# thermostat_hardwork.net
KiCad netlist of a schematic drawn in EasyEDA Pro
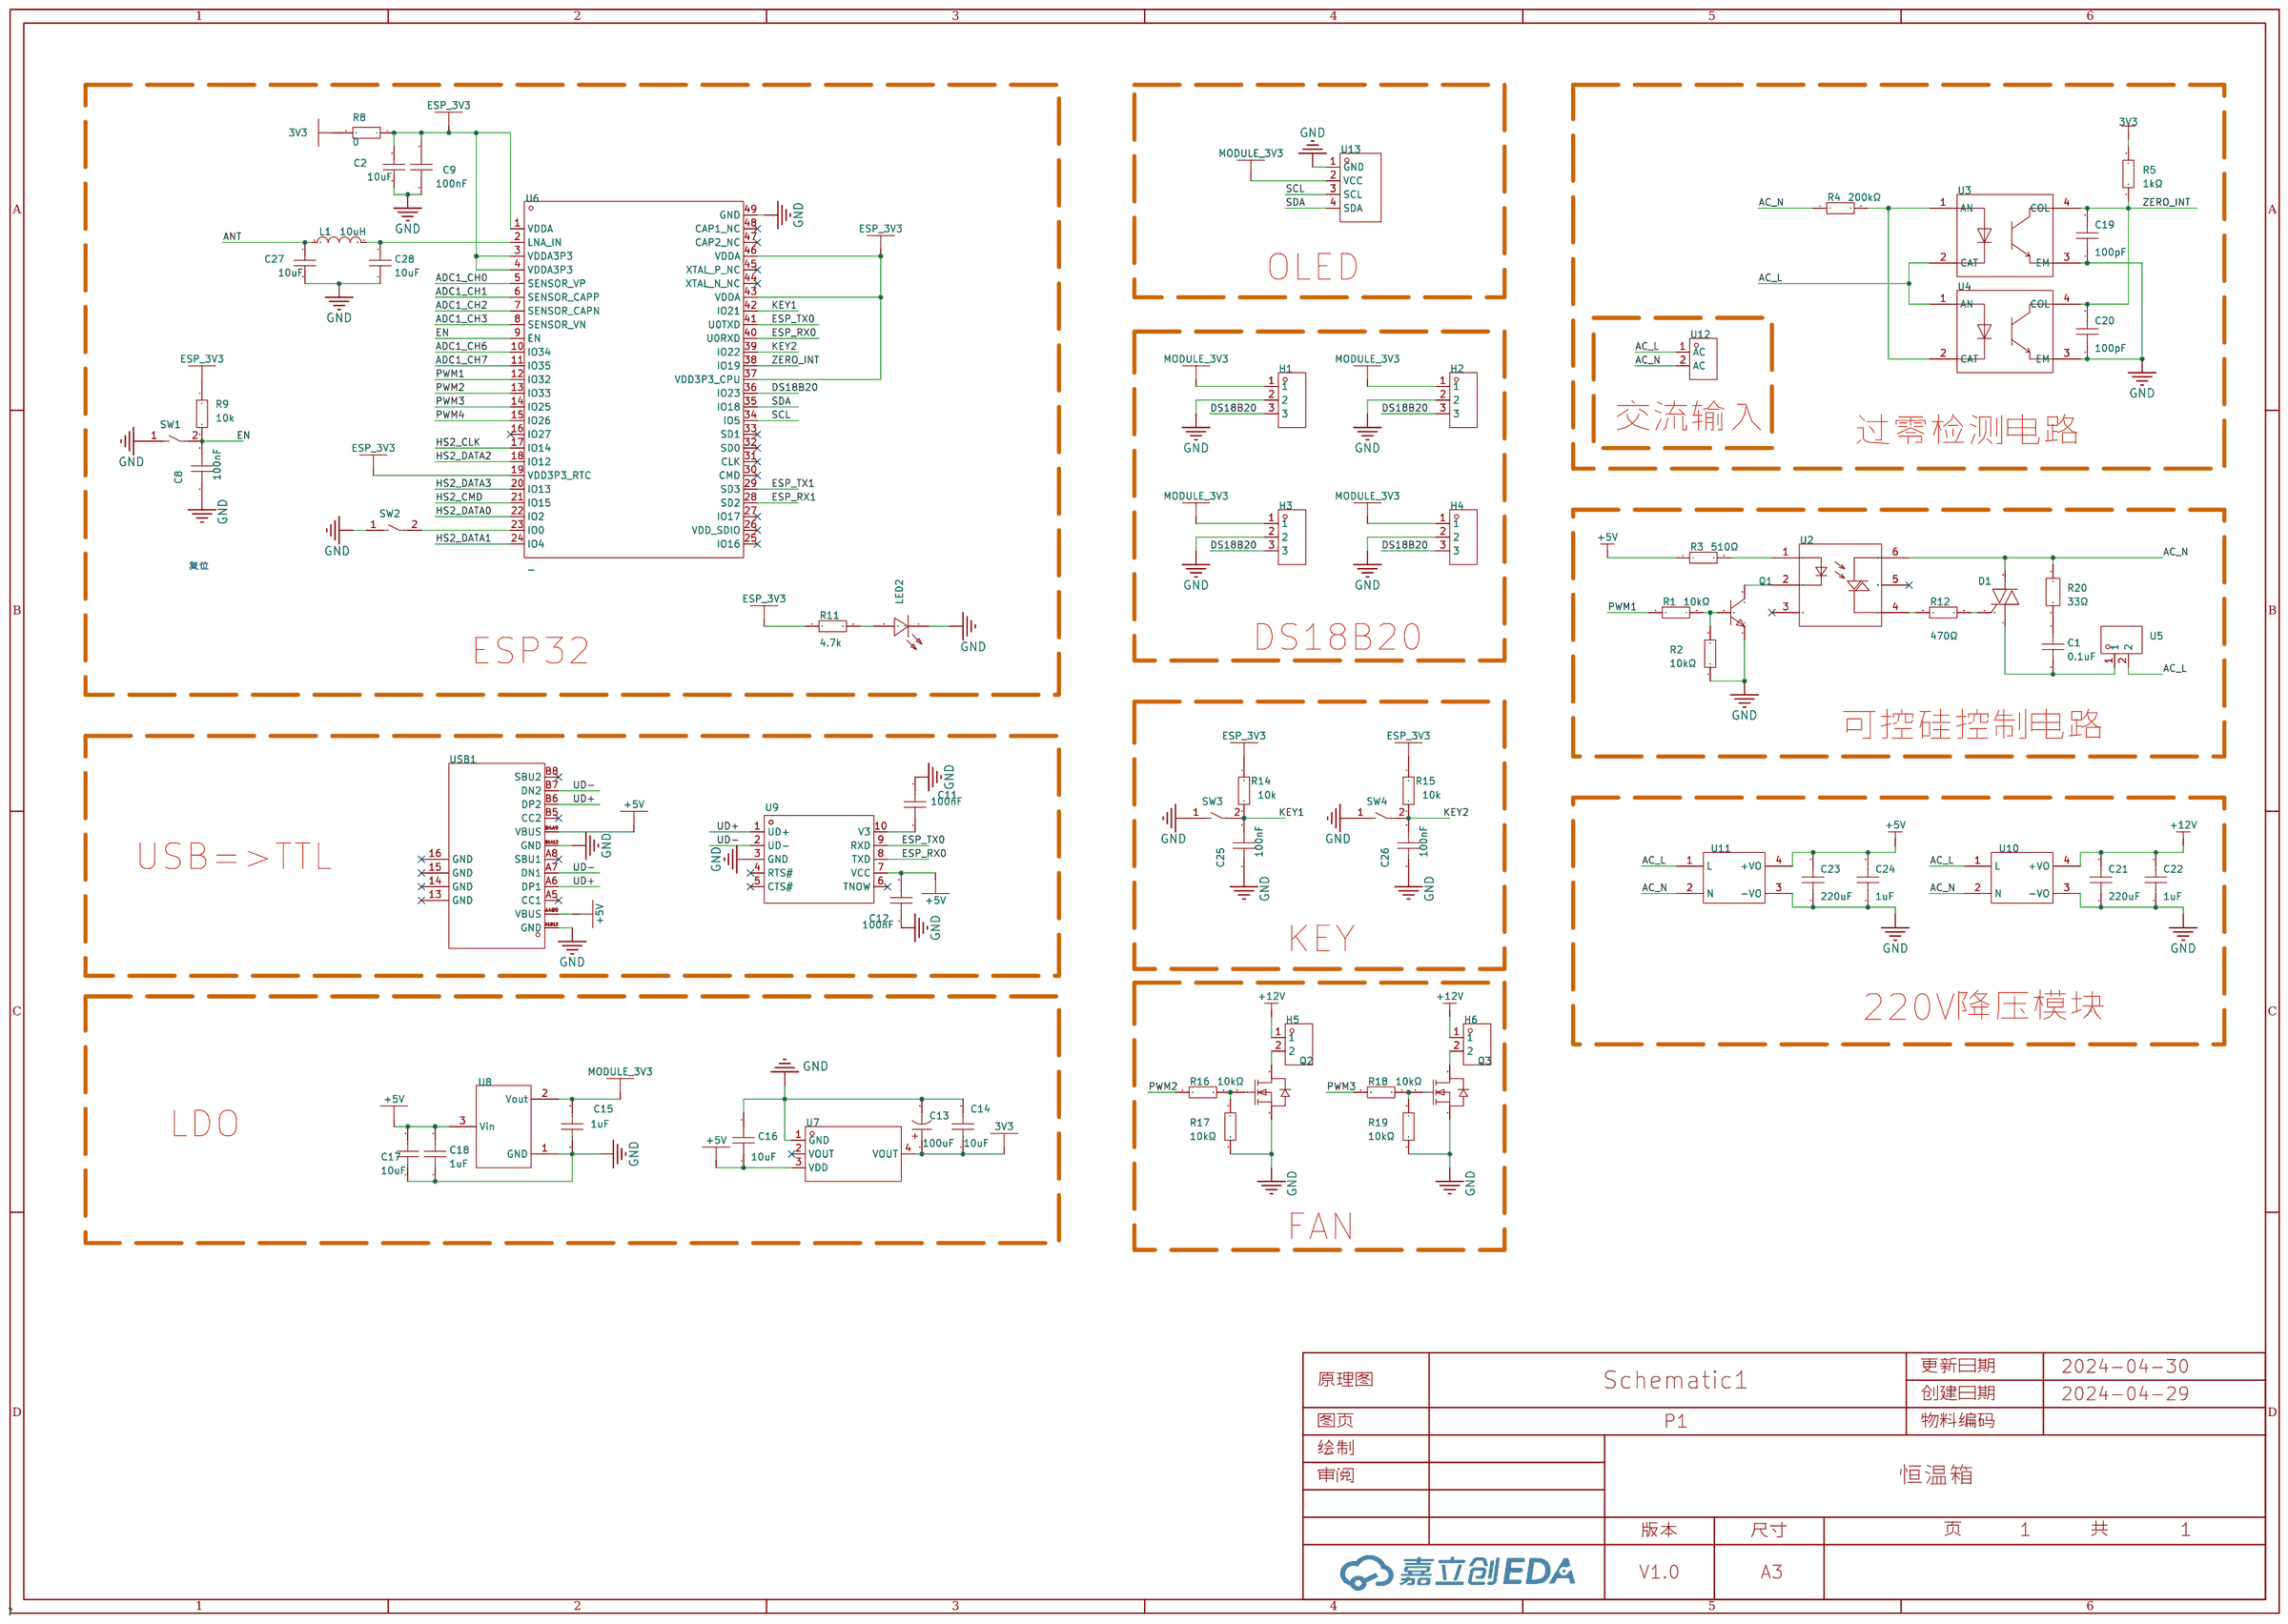
[diagram p0: schematic sheet]

(export (version "E")
  (design (tool "Eeschema 10.0.6"))
  (components
    (comp (ref "C1")
      (value "0.1uF")
      (footprint "easyedapro:C1210")
      (description "容值:10nF;精度:±5%;额定电压:250V;材质(温度系数):C0G;")
      (fields (field (name "Manufacturer Part") "C3225C0G2E103JT000N") (field (name "Manufacturer") "TDK"))
      (libsource (lib "easyedapro") (part "C3225C0G2E103JT000N"))
    )
    (comp (ref "C2")
      (value "10uF")
      (footprint "easyedapro:C0402")
      (description "容值:10uF;精度:±20%;额定电压:6.3V;温度系数:X5R;")
      (fields
        (field (name "Manufacturer Part") "CC0402MRX5R5BB106")
        (field (name "Manufacturer") "YAGEO(国巨)")
      )
      (libsource (lib "easyedapro") (part "CC0402MRX5R5BB106"))
    )
    (comp (ref "C8")
      (value "100nF")
      (description "容值:100nF;精度:±5%;额定电压:16V;温度系数:X7R;")
      (fields
        (field (name "Manufacturer Part") "CC0402JRX7R7BB104")
        (field (name "Manufacturer") "YAGEO(国巨)")
      )
      (libsource (lib "easyedapro") (part "CC0402JRX7R7BB104"))
    )
    (comp (ref "C9")
      (value "100nF")
      (description "容值:100nF;精度:±5%;额定电压:16V;温度系数:X7R;")
      (fields
        (field (name "Manufacturer Part") "CC0402JRX7R7BB104")
        (field (name "Manufacturer") "YAGEO(国巨)")
      )
      (libsource (lib "easyedapro") (part "CC0402JRX7R7BB104"))
    )
    (comp (ref "C11")
      (value "100nF")
      (description "容值:100nF;精度:±5%;额定电压:16V;温度系数:X7R;")
      (fields
        (field (name "Manufacturer Part") "CC0402JRX7R7BB104")
        (field (name "Manufacturer") "YAGEO(国巨)")
      )
      (libsource (lib "easyedapro") (part "CC0402JRX7R7BB104"))
    )
    (comp (ref "C12")
      (value "100nF")
      (description "容值:100nF;精度:±5%;额定电压:16V;温度系数:X7R;")
      (fields
        (field (name "Manufacturer Part") "CC0402JRX7R7BB104")
        (field (name "Manufacturer") "YAGEO(国巨)")
      )
      (libsource (lib "easyedapro") (part "CC0402JRX7R7BB104"))
    )
    (comp (ref "C13")
      (value "100uF")
      (description "容值:100uF;精度:±20%;额定电压:6.3V;等效串联电阻:-;工作温度:-55~+125;")
      (fields
        (field (name "Manufacturer Part") "CA45B-B-6.3V-100uF-M")
        (field (name "Manufacturer") "CEC(振华新云)")
      )
      (libsource (lib "easyedapro") (part "CA45B-B-6.3V-100UF-M"))
    )
    (comp (ref "C14")
      (value "10uF")
      (description "容值:10uF;精度:±10%;额定电压:10V;温度系数:X5R;")
      (fields
        (field (name "Manufacturer Part") "CL10A106KP8NNNC")
        (field (name "Manufacturer") "SAMSUNG(三星)")
      )
      (libsource (lib "easyedapro") (part "CL10A106KP8NNNC"))
    )
    (comp (ref "C15")
      (value "1uF")
      (footprint "easyedapro:C0402")
      (description "容值:1uF;精度:±10%;额定电压:10V;温度系数:X7R;")
      (fields
        (field (name "Manufacturer Part") "GRM155Z71A105KE01D")
        (field (name "Manufacturer") "muRata(村田)")
      )
      (libsource (lib "easyedapro") (part "GRM155Z71A105KE01D"))
    )
    (comp (ref "C16")
      (value "10uF")
      (description "容值:10uF;精度:±10%;额定电压:10V;温度系数:X5R;")
      (fields
        (field (name "Manufacturer Part") "CL10A106KP8NNNC")
        (field (name "Manufacturer") "SAMSUNG(三星)")
      )
      (libsource (lib "easyedapro") (part "CL10A106KP8NNNC"))
    )
    (comp (ref "C17")
      (value "10uF")
      (description "容值:10uF;精度:±10%;额定电压:10V;温度系数:X5R;")
      (fields
        (field (name "Manufacturer Part") "CL10A106KP8NNNC")
        (field (name "Manufacturer") "SAMSUNG(三星)")
      )
      (libsource (lib "easyedapro") (part "CL10A106KP8NNNC"))
    )
    (comp (ref "C18")
      (value "1uF")
      (footprint "easyedapro:C0402")
      (description "容值:1uF;精度:±10%;额定电压:10V;温度系数:X7R;")
      (fields
        (field (name "Manufacturer Part") "GRM155Z71A105KE01D")
        (field (name "Manufacturer") "muRata(村田)")
      )
      (libsource (lib "easyedapro") (part "GRM155Z71A105KE01D"))
    )
    (comp (ref "C19")
      (value "100pF")
      (description "容值:100nF;精度:±5%;额定电压:16V;温度系数:X7R;")
      (fields
        (field (name "Manufacturer Part") "CC0402JRX7R7BB104")
        (field (name "Manufacturer") "YAGEO(国巨)")
      )
      (libsource (lib "easyedapro") (part "CC0402JRX7R7BB104"))
    )
    (comp (ref "C20")
      (value "100pF")
      (description "容值:100nF;精度:±5%;额定电压:16V;温度系数:X7R;")
      (fields
        (field (name "Manufacturer Part") "CC0402JRX7R7BB104")
        (field (name "Manufacturer") "YAGEO(国巨)")
      )
      (libsource (lib "easyedapro") (part "CC0402JRX7R7BB104"))
    )
    (comp (ref "C21")
      (value "220uF")
      (description "容值:100nF;精度:±5%;额定电压:16V;温度系数:X7R;")
      (fields
        (field (name "Manufacturer Part") "CC0402JRX7R7BB104")
        (field (name "Manufacturer") "YAGEO(国巨)")
      )
      (libsource (lib "easyedapro") (part "CC0402JRX7R7BB104"))
    )
    (comp (ref "C22")
      (value "1uF")
      (description "容值:100nF;精度:±5%;额定电压:16V;温度系数:X7R;")
      (fields
        (field (name "Manufacturer Part") "CC0402JRX7R7BB104")
        (field (name "Manufacturer") "YAGEO(国巨)")
      )
      (libsource (lib "easyedapro") (part "CC0402JRX7R7BB104"))
    )
    (comp (ref "C23")
      (value "220uF")
      (description "容值:100nF;精度:±5%;额定电压:16V;温度系数:X7R;")
      (fields
        (field (name "Manufacturer Part") "CC0402JRX7R7BB104")
        (field (name "Manufacturer") "YAGEO(国巨)")
      )
      (libsource (lib "easyedapro") (part "CC0402JRX7R7BB104"))
    )
    (comp (ref "C24")
      (value "1uF")
      (description "容值:100nF;精度:±5%;额定电压:16V;温度系数:X7R;")
      (fields
        (field (name "Manufacturer Part") "CC0402JRX7R7BB104")
        (field (name "Manufacturer") "YAGEO(国巨)")
      )
      (libsource (lib "easyedapro") (part "CC0402JRX7R7BB104"))
    )
    (comp (ref "C25")
      (value "100nF")
      (description "容值:100nF;精度:±5%;额定电压:16V;温度系数:X7R;")
      (fields
        (field (name "Manufacturer Part") "CC0402JRX7R7BB104")
        (field (name "Manufacturer") "YAGEO(国巨)")
      )
      (libsource (lib "easyedapro") (part "CC0402JRX7R7BB104"))
    )
    (comp (ref "C26")
      (value "100nF")
      (description "容值:100nF;精度:±5%;额定电压:16V;温度系数:X7R;")
      (fields
        (field (name "Manufacturer Part") "CC0402JRX7R7BB104")
        (field (name "Manufacturer") "YAGEO(国巨)")
      )
      (libsource (lib "easyedapro") (part "CC0402JRX7R7BB104"))
    )
    (comp (ref "C27")
      (value "10uF")
      (footprint "easyedapro:C0402")
      (description "容值:10uF;精度:±20%;额定电压:6.3V;温度系数:X5R;")
      (fields
        (field (name "Manufacturer Part") "CC0402MRX5R5BB106")
        (field (name "Manufacturer") "YAGEO(国巨)")
      )
      (libsource (lib "easyedapro") (part "CC0402MRX5R5BB106"))
    )
    (comp (ref "C28")
      (value "10uF")
      (footprint "easyedapro:C0402")
      (description "容值:10uF;精度:±20%;额定电压:6.3V;温度系数:X5R;")
      (fields
        (field (name "Manufacturer Part") "CC0402MRX5R5BB106")
        (field (name "Manufacturer") "YAGEO(国巨)")
      )
      (libsource (lib "easyedapro") (part "CC0402MRX5R5BB106"))
    )
    (comp (ref "D1")
      (value "BT136S")
      (footprint "easyedapro:TO-252-3_L6.5-W5.8-P4.58-BL")
      (description "长电双向可控硅")
      (fields (field (name "Manufacturer") "CJ(江苏长电/长晶)"))
      (libsource (lib "easyedapro") (part "BT136S"))
    )
    (comp (ref "H1")
      (value "PZ254V-11-03P")
      (footprint "easyedapro:HDR-TH_3P-P2.54-V-M")
      (fields (field (name "Manufacturer") "XFCN(兴飞)"))
      (libsource (lib "easyedapro") (part "PZ254V-11-03P_C2937625"))
    )
    (comp (ref "H2")
      (value "PZ254V-11-03P")
      (footprint "easyedapro:HDR-TH_3P-P2.54-V-M")
      (fields (field (name "Manufacturer") "XFCN(兴飞)"))
      (libsource (lib "easyedapro") (part "PZ254V-11-03P_C2937625"))
    )
    (comp (ref "H3")
      (value "PZ254V-11-03P")
      (footprint "easyedapro:HDR-TH_3P-P2.54-V-M")
      (fields (field (name "Manufacturer") "XFCN(兴飞)"))
      (libsource (lib "easyedapro") (part "PZ254V-11-03P_C2937625"))
    )
    (comp (ref "H4")
      (value "PZ254V-11-03P")
      (footprint "easyedapro:HDR-TH_3P-P2.54-V-M")
      (fields (field (name "Manufacturer") "XFCN(兴飞)"))
      (libsource (lib "easyedapro") (part "PZ254V-11-03P_C2937625"))
    )
    (comp (ref "H5")
      (value "PZ254V-11-02P")
      (footprint "easyedapro:HDR-TH_2P-P2.54-V-M")
      (fields (field (name "Manufacturer") "XFCN(兴飞)"))
      (libsource (lib "easyedapro") (part "PZ254V-11-02P"))
    )
    (comp (ref "H6")
      (value "PZ254V-11-02P")
      (footprint "easyedapro:HDR-TH_2P-P2.54-V-M")
      (fields (field (name "Manufacturer") "XFCN(兴飞)"))
      (libsource (lib "easyedapro") (part "PZ254V-11-02P"))
    )
    (comp (ref "L1")
      (value "10uH")
      (footprint "easyedapro:L0603")
      (description "电感值:10uH;精度:±10%;额定电流:280mA;直流电阻(DCR):2.4Ω;")
      (fields (field (name "Manufacturer Part") "AHW1608FE100KTF") (field (name "Manufacturer") "APV(爱普微)"))
      (libsource (lib "easyedapro") (part "AHW1608FE100KTF"))
    )
    (comp (ref "LED2")
      (value "~")
      (description "发光颜色:翠绿;")
      (fields (field (name "Manufacturer Part") "NCD0402G1") (field (name "Manufacturer") "国星光电"))
      (libsource (lib "easyedapro") (part "FC-F1005UGK-520M5"))
    )
    (comp (ref "Q1")
      (value "S8050")
      (footprint "easyedapro:SOT-23-3_L2.9-W1.3-P1.90-LS2.4-BR")
      (description "晶体管类型:NPN;集电极电流(Ic):500mA;集射极击穿电压(Vceo):25V;功率(Pd):300mW;")
      (fields (field (name "Manufacturer") "YONGYUTAI(永裕泰)"))
      (libsource (lib "easyedapro") (part "S8050_C2891804"))
    )
    (comp (ref "Q2")
      (value "AO3400A")
      (footprint "easyedapro:SOT-23-3_L2.9-W1.6-P1.90-LS2.8-BR")
      (fields (field (name "Manufacturer") "AOS"))
      (libsource (lib "easyedapro") (part "AO3400A"))
    )
    (comp (ref "Q3")
      (value "AO3400A")
      (footprint "easyedapro:SOT-23-3_L2.9-W1.6-P1.90-LS2.8-BR")
      (fields (field (name "Manufacturer") "AOS"))
      (libsource (lib "easyedapro") (part "AO3400A"))
    )
    (comp (ref "R1")
      (value "10kΩ")
      (footprint "easyedapro:R0603")
      (description "电阻类型:厚膜电阻;阻值:10kΩ;精度:±1%;功率:100mW;最大工作电压:75V;温度系数:±100ppm/°C;")
      (fields
        (field (name "Manufacturer Part") "0603WAF1002T5E")
        (field (name "Manufacturer") "UNI-ROYAL(厚声)")
      )
      (libsource (lib "easyedapro") (part "0603WAF1002T5E"))
    )
    (comp (ref "R2")
      (value "10kΩ")
      (footprint "easyedapro:R0603")
      (description "电阻类型:厚膜电阻;阻值:10kΩ;精度:±1%;功率:100mW;最大工作电压:75V;温度系数:±100ppm/°C;")
      (fields
        (field (name "Manufacturer Part") "0603WAF1002T5E")
        (field (name "Manufacturer") "UNI-ROYAL(厚声)")
      )
      (libsource (lib "easyedapro") (part "0603WAF1002T5E"))
    )
    (comp (ref "R3")
      (value "510Ω")
      (footprint "easyedapro:R0603")
      (description "电阻类型:厚膜电阻;阻值:10kΩ;精度:±1%;功率:100mW;最大工作电压:75V;温度系数:±100ppm/°C;")
      (fields
        (field (name "Manufacturer Part") "0603WAF1002T5E")
        (field (name "Manufacturer") "UNI-ROYAL(厚声)")
      )
      (libsource (lib "easyedapro") (part "0603WAF1002T5E"))
    )
    (comp (ref "R4")
      (value "200kΩ")
      (footprint "easyedapro:R0603")
      (description "电阻类型:厚膜电阻;阻值:200kΩ;精度:±1%;功率:100mW;最大工作电压:75V;温度系数:±100ppm/°C;")
      (fields
        (field (name "Manufacturer Part") "0603WAF2003T5E")
        (field (name "Manufacturer") "UNI-ROYAL(厚声)")
      )
      (libsource (lib "easyedapro") (part "0603WAF2003T5E"))
    )
    (comp (ref "R5")
      (value "1kΩ")
      (footprint "easyedapro:R0603")
      (description "电阻类型:厚膜电阻;阻值:1kΩ;精度:±1%;功率:100mW;最大工作电压:75V;温度系数:±100ppm/°C;")
      (fields (field (name "Manufacturer Part") "RC0603FR-071KL") (field (name "Manufacturer") "YAGEO(国巨)"))
      (libsource (lib "easyedapro") (part "RC0603FR-071KL"))
    )
    (comp (ref "R8")
      (value "0")
      (description "电阻类型:厚膜电阻;阻值:0;精度:±5%;功率:1/16W;温度系数:-;最大工作电压:50V;工作温度范围:-55~+155;")
      (fields
        (field (name "Manufacturer Part") "0402WGJ0000TCE")
        (field (name "Manufacturer") "UNI-ROYAL(厚声)")
      )
      (libsource (lib "easyedapro") (part "0402WGJ0000TCE"))
    )
    (comp (ref "R9")
      (value "10k")
      (description "电阻类型:厚膜电阻;阻值:10k;精度:±1%;功率:62.5mW;温度系数:±100ppm/;最大工作电压:50V;工作温度范围:-55~+155;")
      (fields (field (name "Manufacturer Part") "AC0402FR-0710KL") (field (name "Manufacturer") "YAGEO(国巨)"))
      (libsource (lib "easyedapro") (part "AC0402FR-0710KL"))
    )
    (comp (ref "R11")
      (value "4.7k")
      (description "电阻类型:厚膜电阻;阻值:4.7k;精度:±1%;功率:62.5mW;温度系数:±100ppm/;最大工作电压:50V;工作温度范围:-55~+155;")
      (fields (field (name "Manufacturer Part") "AC0402FR-074K7L") (field (name "Manufacturer") "YAGEO(国巨)"))
      (libsource (lib "easyedapro") (part "AC0402FR-074K7L"))
    )
    (comp (ref "R12")
      (value "470Ω")
      (footprint "easyedapro:R1206")
      (description "电阻类型:厚膜电阻;阻值:22Ω;精度:±1%;功率:250mW;最大工作电压:200V;温度系数:±100ppm/°C;")
      (fields
        (field (name "Manufacturer Part") "1206W4F220JT5E")
        (field (name "Manufacturer") "UNI-ROYAL(厚声)")
      )
      (libsource (lib "easyedapro") (part "1206W4F220JT5E"))
    )
    (comp (ref "R14")
      (value "10k")
      (description "电阻类型:厚膜电阻;阻值:10k;精度:±1%;功率:62.5mW;温度系数:±100ppm/;最大工作电压:50V;工作温度范围:-55~+155;")
      (fields (field (name "Manufacturer Part") "AC0402FR-0710KL") (field (name "Manufacturer") "YAGEO(国巨)"))
      (libsource (lib "easyedapro") (part "AC0402FR-0710KL"))
    )
    (comp (ref "R15")
      (value "10k")
      (description "电阻类型:厚膜电阻;阻值:10k;精度:±1%;功率:62.5mW;温度系数:±100ppm/;最大工作电压:50V;工作温度范围:-55~+155;")
      (fields (field (name "Manufacturer Part") "AC0402FR-0710KL") (field (name "Manufacturer") "YAGEO(国巨)"))
      (libsource (lib "easyedapro") (part "AC0402FR-0710KL"))
    )
    (comp (ref "R16")
      (value "10kΩ")
      (footprint "easyedapro:R0603")
      (description "电阻类型:厚膜电阻;阻值:10kΩ;精度:±1%;功率:100mW;最大工作电压:75V;温度系数:±100ppm/°C;")
      (fields
        (field (name "Manufacturer Part") "0603WAF1002T5E")
        (field (name "Manufacturer") "UNI-ROYAL(厚声)")
      )
      (libsource (lib "easyedapro") (part "0603WAF1002T5E"))
    )
    (comp (ref "R17")
      (value "10kΩ")
      (footprint "easyedapro:R0603")
      (description "电阻类型:厚膜电阻;阻值:10kΩ;精度:±1%;功率:100mW;最大工作电压:75V;温度系数:±100ppm/°C;")
      (fields
        (field (name "Manufacturer Part") "0603WAF1002T5E")
        (field (name "Manufacturer") "UNI-ROYAL(厚声)")
      )
      (libsource (lib "easyedapro") (part "0603WAF1002T5E"))
    )
    (comp (ref "R18")
      (value "10kΩ")
      (footprint "easyedapro:R0603")
      (description "电阻类型:厚膜电阻;阻值:10kΩ;精度:±1%;功率:100mW;最大工作电压:75V;温度系数:±100ppm/°C;")
      (fields
        (field (name "Manufacturer Part") "0603WAF1002T5E")
        (field (name "Manufacturer") "UNI-ROYAL(厚声)")
      )
      (libsource (lib "easyedapro") (part "0603WAF1002T5E"))
    )
    (comp (ref "R19")
      (value "10kΩ")
      (footprint "easyedapro:R0603")
      (description "电阻类型:厚膜电阻;阻值:10kΩ;精度:±1%;功率:100mW;最大工作电压:75V;温度系数:±100ppm/°C;")
      (fields
        (field (name "Manufacturer Part") "0603WAF1002T5E")
        (field (name "Manufacturer") "UNI-ROYAL(厚声)")
      )
      (libsource (lib "easyedapro") (part "0603WAF1002T5E"))
    )
    (comp (ref "R20")
      (value "33Ω")
      (footprint "easyedapro:RES-SMD_L6.4-W3.2-R2512")
      (description "电阻类型:采样电阻;阻值:10mΩ;精度:±1%;功率:3W;安装方式:贴片;")
      (fields
        (field (name "Manufacturer Part") "HoJLR2512-3W-10mR-1%")
        (field (name "Manufacturer") "Milliohm(毫欧)")
      )
      (libsource (lib "easyedapro") (part "HOJLR2512-3W-10MR-1%"))
    )
    (comp (ref "SW1")
      (value "~")
      (description "3*4正按小龟 2脚/两脚贴片小龟 无柱/不带柱")
      (fields
        (field (name "Manufacturer Part") "TS342A2P 250gf-WZ 021")
        (field (name "Manufacturer") "SHOU HAN(首韩)")
      )
      (libsource (lib "easyedapro") (part "TS342A2P 250GF-WZ 021"))
    )
    (comp (ref "SW2")
      (value "~")
      (description "3*4正按小龟 2脚/两脚贴片小龟 无柱/不带柱")
      (fields
        (field (name "Manufacturer Part") "TS342A2P 250gf-WZ 021")
        (field (name "Manufacturer") "SHOU HAN(首韩)")
      )
      (libsource (lib "easyedapro") (part "TS342A2P 250GF-WZ 021"))
    )
    (comp (ref "SW3")
      (value "~")
      (description "3*4正按小龟 2脚/两脚贴片小龟 无柱/不带柱")
      (fields
        (field (name "Manufacturer Part") "TS342A2P 250gf-WZ 021")
        (field (name "Manufacturer") "SHOU HAN(首韩)")
      )
      (libsource (lib "easyedapro") (part "TS342A2P 250GF-WZ 021"))
    )
    (comp (ref "SW4")
      (value "~")
      (description "3*4正按小龟 2脚/两脚贴片小龟 无柱/不带柱")
      (fields
        (field (name "Manufacturer Part") "TS342A2P 250gf-WZ 021")
        (field (name "Manufacturer") "SHOU HAN(首韩)")
      )
      (libsource (lib "easyedapro") (part "TS342A2P 250GF-WZ 021"))
    )
    (comp (ref "U2")
      (value "MOC3052SM")
      (footprint "easyedapro:SMD-6_L7.1-W6.5-P2.54-LS10.3-TL")
      (fields (field (name "Manufacturer") "UMW(友台半导体)"))
      (libsource (lib "easyedapro") (part "MOC3052SM_C3014301"))
    )
    (comp (ref "U3")
      (value "TLP521-1XSM")
      (footprint "easyedapro:SMD-4_L4.6-W6.5-P2.54-LS10.2-BL")
      (fields (field (name "Manufacturer") "ISOCOM(英国安数光)"))
      (libsource (lib "easyedapro") (part "TLP521-1XSM"))
    )
    (comp (ref "U4")
      (value "TLP521-1XSM")
      (footprint "easyedapro:SMD-4_L4.6-W6.5-P2.54-LS10.2-BL")
      (fields (field (name "Manufacturer") "ISOCOM(英国安数光)"))
      (libsource (lib "easyedapro") (part "TLP521-1XSM"))
    )
    (comp (ref "U5")
      (value "KF7.62-2P(green)")
      (footprint "easyedapro:CONN-TH_2P-P7.62_KEFA_KF7.62-2P")
      (fields (field (name "Manufacturer") "KEFA(科发)"))
      (libsource (lib "easyedapro") (part "KF7.62-2P_C5173665"))
    )
    (comp (ref "U6")
      (value "-")
      (footprint "easyedapro:QFN-48_L7.0-W7.0-P0.50-BL-EP5.4")
      (description "类型:-;作业频率:-;输出功率:-;接口类型:-;工作电压:-;")
      (fields (field (name "Manufacturer Part") "ESP32-PICO-D4") (field (name "Manufacturer") "ESPRESSIF 乐鑫"))
      (libsource (lib "easyedapro") (part "ESP32-PICO-D4"))
    )
    (comp (ref "U7")
      (value "~")
      (description "输出类型:-;")
      (fields (field (name "Manufacturer Part") "BL8071CLBTR33") (field (name "Manufacturer") "BL(上海贝岭)"))
      (libsource (lib "easyedapro") (part "BL8071CLBTR33"))
    )
    (comp (ref "U8")
      (value "~")
      (footprint "easyedapro:SOT-23-3_L2.9-W1.6-P1.90-LS2.8-BR")
      (description "输出类型:固定;输出极性:正;输出通道数:1;最大输入电压:6V;输出电压:3.3V;压差:680mV@(100mA);输出电流:200mA;电源纹波抑制比(PRSS):-;")
      (fields (field (name "Manufacturer Part") "XC6206P332MR") (field (name "Manufacturer") "TOREX(特瑞仕)"))
      (libsource (lib "easyedapro") (part "XC6206P332MR"))
    )
    (comp (ref "U9")
      (value "~")
      (footprint "easyedapro:MSOP-10_L3.0-W3.0-P0.50-LS5.0-BL")
      (description "类型:Transceiver;协议类别:USB 2.0;驱动器/接收器数:-;数据速率:2Mbps;")
      (fields (field (name "Manufacturer Part") "CH340E") (field (name "Manufacturer") "WCH(南京沁恒)"))
      (libsource (lib "easyedapro") (part "CH340E"))
    )
    (comp (ref "U10")
      (value "~")
      (footprint "easyedapro:GJ_W_")
      (description "220V降压模块")
      (libsource (lib "easyedapro") (part "GJ_W_"))
    )
    (comp (ref "U11")
      (value "~")
      (footprint "easyedapro:GJ_W_")
      (description "220V降压模块")
      (libsource (lib "easyedapro") (part "GJ_W_"))
    )
    (comp (ref "U12")
      (value "RT-C06-A1B-AC")
      (footprint "easyedapro:CONN-TH_LEGION_RT-C06-A1B-AC")
      (description "带安规认证米老鼠三孔插座1.Rating：2.5A 250VAC UL CUL")
      (fields (field (name "Manufacturer") "Legion(六钧)"))
      (libsource (lib "easyedapro") (part "RT-C06-A1B-AC_C18221846"))
    )
    (comp (ref "U13")
      (value "HS96L03W2C03")
      (footprint "easyedapro:OLED-TH_L27.8-W27.2-P2.54_C9900033791")
      (description "主控芯片:SSD1315;接口类型:I2C;尺寸(inch):0.96;像素分辨率:128x64;")
      (fields (field (name "Manufacturer") "HS(汉昇)"))
      (libsource (lib "easyedapro") (part "HS96L03W2C03"))
    )
    (comp (ref "USB1")
      (value "~")
      (footprint "easyedapro:USB-C-SMD_TYPEC-304-BCP16")
      (description "连接器类型:Type-C;标准:USB 3.1;公母:母座;触点数量:16.0;端口数量:1;安装方式:卧贴;额定电流 - 电源:3A;工作温度范围:-25~+85;焊接温度(最大值):260;")
      (fields (field (name "Manufacturer Part") "TYPEC-304-BCP16") (field (name "Manufacturer") "XUNPU(讯普)"))
      (libsource (lib "easyedapro") (part "TYPEC-304-BCP16"))
    )
  )
  (nets
    (net (code "1") (name "+5V") (class "Default")
      (node (ref "C12") (pin "2") (pinfunction "2_2") (pintype "input"))
      (node (ref "C16") (pin "1") (pinfunction "1_1") (pintype "input"))
      (node (ref "C17") (pin "2") (pinfunction "2_2") (pintype "input"))
      (node (ref "C18") (pin "2") (pinfunction "2_2") (pintype "input"))
      (node (ref "C23") (pin "2") (pinfunction "2_2") (pintype "input"))
      (node (ref "C24") (pin "2") (pinfunction "2_2") (pintype "input"))
      (node (ref "R3") (pin "1") (pinfunction "1_1") (pintype "input"))
      (node (ref "U11") (pin "4") (pinfunction "+VO_4") (pintype "input"))
      (node (ref "U7") (pin "3") (pinfunction "VDD_3") (pintype "input"))
      (node (ref "U8") (pin "3") (pinfunction "Vin_3") (pintype "input"))
      (node (ref "U9") (pin "7") (pinfunction "VCC_7") (pintype "input"))
      (node (ref "USB1") (pin "A4B9") (pinfunction "VBUS_A4B9") (pintype "input"))
      (node (ref "USB1") (pin "B4A9") (pinfunction "VBUS_B4A9") (pintype "input"))
    )
    (net (code "2") (name "+12V") (class "Default")
      (node (ref "C21") (pin "2") (pinfunction "2_2") (pintype "input"))
      (node (ref "C22") (pin "2") (pinfunction "2_2") (pintype "input"))
      (node (ref "H5") (pin "1") (pinfunction "1_1") (pintype "unspecified"))
      (node (ref "H6") (pin "1") (pinfunction "1_1") (pintype "unspecified"))
      (node (ref "U10") (pin "4") (pinfunction "+VO_4") (pintype "input"))
    )
    (net (code "3") (name "/AC_L") (class "Default")
      (node (ref "U10") (pin "1") (pinfunction "L_1") (pintype "input"))
      (node (ref "U11") (pin "1") (pinfunction "L_1") (pintype "input"))
      (node (ref "U12") (pin "1") (pinfunction "AC_1") (pintype "unspecified"))
      (node (ref "U3") (pin "2") (pinfunction "CAT_2") (pintype "unspecified"))
      (node (ref "U4") (pin "1") (pinfunction "AN_1") (pintype "unspecified"))
      (node (ref "U5") (pin "2") (pinfunction "2_2") (pintype "unspecified"))
    )
    (net (code "4") (name "/AC_N") (class "Default")
      (node (ref "D1") (pin "2") (pinfunction "M2_2") (pintype "unspecified"))
      (node (ref "R20") (pin "1") (pinfunction "1_1") (pintype "unspecified"))
      (node (ref "R4") (pin "1") (pinfunction "1_1") (pintype "input"))
      (node (ref "U10") (pin "2") (pinfunction "N_2") (pintype "input"))
      (node (ref "U11") (pin "2") (pinfunction "N_2") (pintype "input"))
      (node (ref "U12") (pin "2") (pinfunction "AC_2") (pintype "unspecified"))
      (node (ref "U2") (pin "6") (pinfunction "Terminal_6") (pintype "unspecified"))
    )
    (net (code "5") (name "/ADC1_CH0") (class "Default")
      (node (ref "U6") (pin "5") (pinfunction "SENSOR_VP_5") (pintype "input"))
    )
    (net (code "6") (name "/ADC1_CH1") (class "Default")
      (node (ref "U6") (pin "6") (pinfunction "SENSOR_CAPP_6") (pintype "input"))
    )
    (net (code "7") (name "/ADC1_CH2") (class "Default")
      (node (ref "U6") (pin "7") (pinfunction "SENSOR_CAPN_7") (pintype "input"))
    )
    (net (code "8") (name "/ADC1_CH3") (class "Default")
      (node (ref "U6") (pin "8") (pinfunction "SENSOR_VN_8") (pintype "input"))
    )
    (net (code "9") (name "/ADC1_CH6") (class "Default")
      (node (ref "U6") (pin "10") (pinfunction "IO34_10") (pintype "input"))
    )
    (net (code "10") (name "/ADC1_CH7") (class "Default")
      (node (ref "U6") (pin "11") (pinfunction "IO35_11") (pintype "input"))
    )
    (net (code "11") (name "/ANT") (class "Default")
      (node (ref "C27") (pin "2") (pinfunction "2_2") (pintype "input"))
      (node (ref "L1") (pin "1") (pinfunction "1_1") (pintype "unspecified"))
    )
    (net (code "12") (name "/DS18B20") (class "Default")
      (node (ref "H1") (pin "3") (pinfunction "3_3") (pintype "unspecified"))
      (node (ref "H2") (pin "3") (pinfunction "3_3") (pintype "unspecified"))
      (node (ref "H3") (pin "3") (pinfunction "3_3") (pintype "unspecified"))
      (node (ref "H4") (pin "3") (pinfunction "3_3") (pintype "unspecified"))
      (node (ref "U6") (pin "36") (pinfunction "IO23_36") (pintype "input"))
    )
    (net (code "13") (name "/EN") (class "Default")
      (node (ref "C8") (pin "2") (pinfunction "2_2") (pintype "input"))
      (node (ref "R9") (pin "2") (pinfunction "2_2") (pintype "input"))
      (node (ref "SW1") (pin "2") (pinfunction "2_2") (pintype "input"))
      (node (ref "U6") (pin "9") (pinfunction "EN_9") (pintype "input"))
    )
    (net (code "14") (name "/ESP_RX0") (class "Default")
      (node (ref "U6") (pin "40") (pinfunction "U0RXD_40") (pintype "input"))
      (node (ref "U9") (pin "8") (pinfunction "TXD_8") (pintype "input"))
    )
    (net (code "15") (name "/ESP_RX1") (class "Default")
      (node (ref "U6") (pin "28") (pinfunction "SD2_28") (pintype "input"))
    )
    (net (code "16") (name "/ESP_TX0") (class "Default")
      (node (ref "U6") (pin "41") (pinfunction "U0TXD_41") (pintype "input"))
      (node (ref "U9") (pin "9") (pinfunction "RXD_9") (pintype "input"))
    )
    (net (code "17") (name "/ESP_TX1") (class "Default")
      (node (ref "U6") (pin "29") (pinfunction "SD3_29") (pintype "input"))
    )
    (net (code "18") (name "/HS2_CLK") (class "Default")
      (node (ref "U6") (pin "17") (pinfunction "IO14_17") (pintype "input"))
    )
    (net (code "19") (name "/HS2_CMD") (class "Default")
      (node (ref "U6") (pin "21") (pinfunction "IO15_21") (pintype "input"))
    )
    (net (code "20") (name "/HS2_DATA0") (class "Default")
      (node (ref "U6") (pin "22") (pinfunction "IO2_22") (pintype "input"))
    )
    (net (code "21") (name "/HS2_DATA1") (class "Default")
      (node (ref "U6") (pin "24") (pinfunction "IO4_24") (pintype "input"))
    )
    (net (code "22") (name "/HS2_DATA2") (class "Default")
      (node (ref "U6") (pin "18") (pinfunction "IO12_18") (pintype "input"))
    )
    (net (code "23") (name "/HS2_DATA3") (class "Default")
      (node (ref "U6") (pin "20") (pinfunction "IO13_20") (pintype "input"))
    )
    (net (code "24") (name "/KEY1") (class "Default")
      (node (ref "C25") (pin "2") (pinfunction "2_2") (pintype "input"))
      (node (ref "R14") (pin "2") (pinfunction "2_2") (pintype "input"))
      (node (ref "SW3") (pin "2") (pinfunction "2_2") (pintype "input"))
      (node (ref "U6") (pin "42") (pinfunction "IO21_42") (pintype "input"))
    )
    (net (code "25") (name "/KEY2") (class "Default")
      (node (ref "C26") (pin "2") (pinfunction "2_2") (pintype "input"))
      (node (ref "R15") (pin "2") (pinfunction "2_2") (pintype "input"))
      (node (ref "SW4") (pin "2") (pinfunction "2_2") (pintype "input"))
      (node (ref "U6") (pin "39") (pinfunction "IO22_39") (pintype "input"))
    )
    (net (code "26") (name "/PWM1") (class "Default")
      (node (ref "R1") (pin "1") (pinfunction "1_1") (pintype "input"))
      (node (ref "U6") (pin "12") (pinfunction "IO32_12") (pintype "input"))
    )
    (net (code "27") (name "/PWM2") (class "Default")
      (node (ref "R16") (pin "1") (pinfunction "1_1") (pintype "input"))
      (node (ref "U6") (pin "13") (pinfunction "IO33_13") (pintype "input"))
    )
    (net (code "28") (name "/PWM3") (class "Default")
      (node (ref "R18") (pin "1") (pinfunction "1_1") (pintype "input"))
      (node (ref "U6") (pin "14") (pinfunction "IO25_14") (pintype "input"))
    )
    (net (code "29") (name "/PWM4") (class "Default")
      (node (ref "U6") (pin "15") (pinfunction "IO26_15") (pintype "input"))
    )
    (net (code "30") (name "/SCL") (class "Default")
      (node (ref "U13") (pin "3") (pinfunction "SCL_3") (pintype "unspecified"))
      (node (ref "U6") (pin "34") (pinfunction "IO5_34") (pintype "input"))
    )
    (net (code "31") (name "/SDA") (class "Default")
      (node (ref "U13") (pin "4") (pinfunction "SDA_4") (pintype "unspecified"))
      (node (ref "U6") (pin "35") (pinfunction "IO18_35") (pintype "input"))
    )
    (net (code "32") (name "/UD+") (class "Default")
      (node (ref "U9") (pin "1") (pinfunction "UD+_1") (pintype "input"))
      (node (ref "USB1") (pin "A6") (pinfunction "DP1_A6") (pintype "input"))
      (node (ref "USB1") (pin "B6") (pinfunction "DP2_B6") (pintype "input"))
    )
    (net (code "33") (name "/UD-") (class "Default")
      (node (ref "U9") (pin "2") (pinfunction "UD-_2") (pintype "input"))
      (node (ref "USB1") (pin "A7") (pinfunction "DN1_A7") (pintype "input"))
      (node (ref "USB1") (pin "B7") (pinfunction "DN2_B7") (pintype "input"))
    )
    (net (code "34") (name "/ZERO_INT") (class "Default")
      (node (ref "C19") (pin "2") (pinfunction "2_2") (pintype "input"))
      (node (ref "C20") (pin "2") (pinfunction "2_2") (pintype "input"))
      (node (ref "R5") (pin "1") (pinfunction "1_1") (pintype "input"))
      (node (ref "U3") (pin "4") (pinfunction "COL_4") (pintype "unspecified"))
      (node (ref "U4") (pin "4") (pinfunction "COL_4") (pintype "unspecified"))
      (node (ref "U6") (pin "38") (pinfunction "IO19_38") (pintype "input"))
    )
    (net (code "35") (name "3V3") (class "Default")
      (node (ref "C13") (pin "1") (pinfunction "1_1") (pintype "input"))
      (node (ref "C14") (pin "1") (pinfunction "1_1") (pintype "input"))
      (node (ref "R5") (pin "2") (pinfunction "2_2") (pintype "input"))
      (node (ref "R8") (pin "2") (pinfunction "2_2") (pintype "input"))
      (node (ref "U7") (pin "4") (pinfunction "VOUT_4") (pintype "input"))
    )
    (net (code "36") (name "ESP_3V3") (class "Default")
      (node (ref "C2") (pin "2") (pinfunction "2_2") (pintype "input"))
      (node (ref "C9") (pin "2") (pinfunction "2_2") (pintype "input"))
      (node (ref "R11") (pin "1") (pinfunction "1_1") (pintype "input"))
      (node (ref "R14") (pin "1") (pinfunction "1_1") (pintype "input"))
      (node (ref "R15") (pin "1") (pinfunction "1_1") (pintype "input"))
      (node (ref "R8") (pin "1") (pinfunction "1_1") (pintype "input"))
      (node (ref "R9") (pin "1") (pinfunction "1_1") (pintype "input"))
      (node (ref "U6") (pin "1") (pinfunction "VDDA_1") (pintype "input"))
      (node (ref "U6") (pin "19") (pinfunction "VDD3P3_RTC_19") (pintype "input"))
      (node (ref "U6") (pin "3") (pinfunction "VDDA3P3_3") (pintype "input"))
      (node (ref "U6") (pin "37") (pinfunction "VDD3P3_CPU_37") (pintype "input"))
      (node (ref "U6") (pin "4") (pinfunction "VDDA3P3_4") (pintype "input"))
      (node (ref "U6") (pin "43") (pinfunction "VDDA_43") (pintype "input"))
      (node (ref "U6") (pin "46") (pinfunction "VDDA_46") (pintype "input"))
    )
    (net (code "37") (name "GND") (class "Default")
      (node (ref "C11") (pin "2") (pinfunction "2_2") (pintype "input"))
      (node (ref "C12") (pin "1") (pinfunction "1_1") (pintype "input"))
      (node (ref "C13") (pin "2") (pinfunction "2_2") (pintype "input"))
      (node (ref "C14") (pin "2") (pinfunction "2_2") (pintype "input"))
      (node (ref "C15") (pin "1") (pinfunction "1_1") (pintype "input"))
      (node (ref "C16") (pin "2") (pinfunction "2_2") (pintype "input"))
      (node (ref "C17") (pin "1") (pinfunction "1_1") (pintype "input"))
      (node (ref "C18") (pin "1") (pinfunction "1_1") (pintype "input"))
      (node (ref "C19") (pin "1") (pinfunction "1_1") (pintype "input"))
      (node (ref "C2") (pin "1") (pinfunction "1_1") (pintype "input"))
      (node (ref "C20") (pin "1") (pinfunction "1_1") (pintype "input"))
      (node (ref "C21") (pin "1") (pinfunction "1_1") (pintype "input"))
      (node (ref "C22") (pin "1") (pinfunction "1_1") (pintype "input"))
      (node (ref "C23") (pin "1") (pinfunction "1_1") (pintype "input"))
      (node (ref "C24") (pin "1") (pinfunction "1_1") (pintype "input"))
      (node (ref "C25") (pin "1") (pinfunction "1_1") (pintype "input"))
      (node (ref "C26") (pin "1") (pinfunction "1_1") (pintype "input"))
      (node (ref "C27") (pin "1") (pinfunction "1_1") (pintype "input"))
      (node (ref "C28") (pin "1") (pinfunction "1_1") (pintype "input"))
      (node (ref "C8") (pin "1") (pinfunction "1_1") (pintype "input"))
      (node (ref "C9") (pin "1") (pinfunction "1_1") (pintype "input"))
      (node (ref "H1") (pin "2") (pinfunction "2_2") (pintype "unspecified"))
      (node (ref "H2") (pin "2") (pinfunction "2_2") (pintype "unspecified"))
      (node (ref "H3") (pin "2") (pinfunction "2_2") (pintype "unspecified"))
      (node (ref "H4") (pin "2") (pinfunction "2_2") (pintype "unspecified"))
      (node (ref "LED2") (pin "1") (pinfunction "K_1") (pintype "input"))
      (node (ref "Q1") (pin "2") (pinfunction "E_2") (pintype "unspecified"))
      (node (ref "Q2") (pin "2") (pinfunction "S_2") (pintype "unspecified"))
      (node (ref "Q3") (pin "2") (pinfunction "S_2") (pintype "unspecified"))
      (node (ref "R17") (pin "1") (pinfunction "1_1") (pintype "input"))
      (node (ref "R19") (pin "1") (pinfunction "1_1") (pintype "input"))
      (node (ref "R2") (pin "1") (pinfunction "1_1") (pintype "input"))
      (node (ref "SW1") (pin "1") (pinfunction "1_1") (pintype "input"))
      (node (ref "SW2") (pin "1") (pinfunction "1_1") (pintype "input"))
      (node (ref "SW3") (pin "1") (pinfunction "1_1") (pintype "input"))
      (node (ref "SW4") (pin "1") (pinfunction "1_1") (pintype "input"))
      (node (ref "U10") (pin "3") (pinfunction "-VO_3") (pintype "input"))
      (node (ref "U11") (pin "3") (pinfunction "-VO_3") (pintype "input"))
      (node (ref "U13") (pin "1") (pinfunction "GND_1") (pintype "unspecified"))
      (node (ref "U3") (pin "3") (pinfunction "EM_3") (pintype "unspecified"))
      (node (ref "U4") (pin "3") (pinfunction "EM_3") (pintype "unspecified"))
      (node (ref "U6") (pin "49") (pinfunction "GND_49") (pintype "input"))
      (node (ref "U7") (pin "1") (pinfunction "GND_1") (pintype "input"))
      (node (ref "U8") (pin "1") (pinfunction "GND_1") (pintype "input"))
      (node (ref "U9") (pin "3") (pinfunction "GND_3") (pintype "input"))
      (node (ref "USB1") (pin "A1B12") (pinfunction "GND_A1B12") (pintype "input"))
      (node (ref "USB1") (pin "B1A12") (pinfunction "GND_B1A12") (pintype "input"))
    )
    (net (code "38") (name "MODULE_3V3") (class "Default")
      (node (ref "C15") (pin "2") (pinfunction "2_2") (pintype "input"))
      (node (ref "H1") (pin "1") (pinfunction "1_1") (pintype "unspecified"))
      (node (ref "H2") (pin "1") (pinfunction "1_1") (pintype "unspecified"))
      (node (ref "H3") (pin "1") (pinfunction "1_1") (pintype "unspecified"))
      (node (ref "H4") (pin "1") (pinfunction "1_1") (pintype "unspecified"))
      (node (ref "U13") (pin "2") (pinfunction "VCC_2") (pintype "unspecified"))
      (node (ref "U8") (pin "2") (pinfunction "Vout_2") (pintype "input"))
    )
    (net (code "39") (name "Net-(C1-Pad1)") (class "Default")
      (node (ref "C1") (pin "1") (pinfunction "1_1") (pintype "unspecified"))
      (node (ref "R20") (pin "2") (pinfunction "2_2") (pintype "unspecified"))
    )
    (net (code "40") (name "Net-(D1-G)") (class "Default")
      (node (ref "D1") (pin "3") (pinfunction "G_3") (pintype "unspecified"))
      (node (ref "R12") (pin "2") (pinfunction "2_2") (pintype "input"))
    )
    (net (code "41") (name "Net-(D1-M1)") (class "Default")
      (node (ref "C1") (pin "2") (pinfunction "2_2") (pintype "unspecified"))
      (node (ref "D1") (pin "1") (pinfunction "M1_1") (pintype "unspecified"))
      (node (ref "U5") (pin "1") (pinfunction "1_1") (pintype "unspecified"))
    )
    (net (code "42") (name "Net-(LED2-A)") (class "Default")
      (node (ref "LED2") (pin "2") (pinfunction "A_2") (pintype "input"))
      (node (ref "R11") (pin "2") (pinfunction "2_2") (pintype "input"))
    )
    (net (code "43") (name "Net-(Q1-B)") (class "Default")
      (node (ref "Q1") (pin "1") (pinfunction "B_1") (pintype "unspecified"))
      (node (ref "R1") (pin "2") (pinfunction "2_2") (pintype "input"))
      (node (ref "R2") (pin "2") (pinfunction "2_2") (pintype "input"))
    )
    (net (code "44") (name "Net-(Q1-C)") (class "Default")
      (node (ref "Q1") (pin "3") (pinfunction "C_3") (pintype "unspecified"))
      (node (ref "U2") (pin "2") (pinfunction "CAT_2") (pintype "unspecified"))
    )
    (net (code "45") (name "Net-(Q2-D)") (class "Default")
      (node (ref "H5") (pin "2") (pinfunction "2_2") (pintype "unspecified"))
      (node (ref "Q2") (pin "3") (pinfunction "D_3") (pintype "unspecified"))
    )
    (net (code "46") (name "Net-(Q2-G)") (class "Default")
      (node (ref "Q2") (pin "1") (pinfunction "G_1") (pintype "unspecified"))
      (node (ref "R16") (pin "2") (pinfunction "2_2") (pintype "input"))
      (node (ref "R17") (pin "2") (pinfunction "2_2") (pintype "input"))
    )
    (net (code "47") (name "Net-(Q3-D)") (class "Default")
      (node (ref "H6") (pin "2") (pinfunction "2_2") (pintype "unspecified"))
      (node (ref "Q3") (pin "3") (pinfunction "D_3") (pintype "unspecified"))
    )
    (net (code "48") (name "Net-(Q3-G)") (class "Default")
      (node (ref "Q3") (pin "1") (pinfunction "G_1") (pintype "unspecified"))
      (node (ref "R18") (pin "2") (pinfunction "2_2") (pintype "input"))
      (node (ref "R19") (pin "2") (pinfunction "2_2") (pintype "input"))
    )
    (net (code "49") (name "Net-(R12-Pad1)") (class "Default")
      (node (ref "R12") (pin "1") (pinfunction "1_1") (pintype "input"))
      (node (ref "U2") (pin "4") (pinfunction "Terminal_4") (pintype "unspecified"))
    )
    (net (code "50") (name "Net-(U2-AN)") (class "Default")
      (node (ref "R3") (pin "2") (pinfunction "2_2") (pintype "input"))
      (node (ref "U2") (pin "1") (pinfunction "AN_1") (pintype "unspecified"))
    )
    (net (code "51") (name "Net-(U3-AN)") (class "Default")
      (node (ref "R4") (pin "2") (pinfunction "2_2") (pintype "input"))
      (node (ref "U3") (pin "1") (pinfunction "AN_1") (pintype "unspecified"))
      (node (ref "U4") (pin "2") (pinfunction "CAT_2") (pintype "unspecified"))
    )
    (net (code "52") (name "Net-(U6-IO0)") (class "Default")
      (node (ref "SW2") (pin "2") (pinfunction "2_2") (pintype "input"))
      (node (ref "U6") (pin "23") (pinfunction "IO0_23") (pintype "input"))
    )
    (net (code "53") (name "Net-(U6-LNA_IN)") (class "Default")
      (node (ref "C28") (pin "2") (pinfunction "2_2") (pintype "input"))
      (node (ref "L1") (pin "2") (pinfunction "2_2") (pintype "unspecified"))
      (node (ref "U6") (pin "2") (pinfunction "LNA_IN_2") (pintype "input"))
    )
    (net (code "54") (name "Net-(U9-V3)") (class "Default")
      (node (ref "C11") (pin "1") (pinfunction "1_1") (pintype "input"))
      (node (ref "U9") (pin "10") (pinfunction "V3_10") (pintype "input"))
    )
    (net (code "55") (name "unconnected-(U2-NC-Pad3)") (class "Default")
      (node (ref "U2") (pin "3") (pinfunction "NC_3") (pintype "unspecified+no_connect"))
    )
    (net (code "56") (name "unconnected-(U2-Substrate-Pad5)") (class "Default")
      (node (ref "U2") (pin "5") (pinfunction "Substrate_5") (pintype "unspecified+no_connect"))
    )
    (net (code "57") (name "unconnected-(U6-CAP1_NC-Pad48)") (class "Default")
      (node (ref "U6") (pin "48") (pinfunction "CAP1_NC_48") (pintype "input+no_connect"))
    )
    (net (code "58") (name "unconnected-(U6-CAP2_NC-Pad47)") (class "Default")
      (node (ref "U6") (pin "47") (pinfunction "CAP2_NC_47") (pintype "input+no_connect"))
    )
    (net (code "59") (name "unconnected-(U6-CLK-Pad31)") (class "Default")
      (node (ref "U6") (pin "31") (pinfunction "CLK_31") (pintype "input+no_connect"))
    )
    (net (code "60") (name "unconnected-(U6-CMD-Pad30)") (class "Default")
      (node (ref "U6") (pin "30") (pinfunction "CMD_30") (pintype "input+no_connect"))
    )
    (net (code "61") (name "unconnected-(U6-IO16-Pad25)") (class "Default")
      (node (ref "U6") (pin "25") (pinfunction "IO16_25") (pintype "input+no_connect"))
    )
    (net (code "62") (name "unconnected-(U6-IO17-Pad27)") (class "Default")
      (node (ref "U6") (pin "27") (pinfunction "IO17_27") (pintype "input+no_connect"))
    )
    (net (code "63") (name "unconnected-(U6-IO27-Pad16)") (class "Default")
      (node (ref "U6") (pin "16") (pinfunction "IO27_16") (pintype "input+no_connect"))
    )
    (net (code "64") (name "unconnected-(U6-SD0-Pad32)") (class "Default")
      (node (ref "U6") (pin "32") (pinfunction "SD0_32") (pintype "input+no_connect"))
    )
    (net (code "65") (name "unconnected-(U6-SD1-Pad33)") (class "Default")
      (node (ref "U6") (pin "33") (pinfunction "SD1_33") (pintype "input+no_connect"))
    )
    (net (code "66") (name "unconnected-(U6-VDD_SDIO-Pad26)") (class "Default")
      (node (ref "U6") (pin "26") (pinfunction "VDD_SDIO_26") (pintype "input+no_connect"))
    )
    (net (code "67") (name "unconnected-(U6-XTAL_N_NC-Pad44)") (class "Default")
      (node (ref "U6") (pin "44") (pinfunction "XTAL_N_NC_44") (pintype "input+no_connect"))
    )
    (net (code "68") (name "unconnected-(U6-XTAL_P_NC-Pad45)") (class "Default")
      (node (ref "U6") (pin "45") (pinfunction "XTAL_P_NC_45") (pintype "input+no_connect"))
    )
    (net (code "69") (name "unconnected-(U7-VOUT-Pad2)") (class "Default")
      (node (ref "U7") (pin "2") (pinfunction "VOUT_2") (pintype "input+no_connect"))
    )
    (net (code "70") (name "unconnected-(U9-CTS#-Pad5)") (class "Default")
      (node (ref "U9") (pin "5") (pinfunction "CTS#_5") (pintype "input+no_connect"))
    )
    (net (code "71") (name "unconnected-(U9-RTS#-Pad4)") (class "Default")
      (node (ref "U9") (pin "4") (pinfunction "RTS#_4") (pintype "input+no_connect"))
    )
    (net (code "72") (name "unconnected-(U9-TNOW-Pad6)") (class "Default")
      (node (ref "U9") (pin "6") (pinfunction "TNOW_6") (pintype "input+no_connect"))
    )
    (net (code "73") (name "unconnected-(USB1-CC1-PadA5)") (class "Default")
      (node (ref "USB1") (pin "A5") (pinfunction "CC1_A5") (pintype "input+no_connect"))
    )
    (net (code "74") (name "unconnected-(USB1-CC2-PadB5)") (class "Default")
      (node (ref "USB1") (pin "B5") (pinfunction "CC2_B5") (pintype "input+no_connect"))
    )
    (net (code "75") (name "unconnected-(USB1-GND-Pad13)") (class "Default")
      (node (ref "USB1") (pin "13") (pinfunction "GND_13") (pintype "input+no_connect"))
    )
    (net (code "76") (name "unconnected-(USB1-GND-Pad14)") (class "Default")
      (node (ref "USB1") (pin "14") (pinfunction "GND_14") (pintype "input+no_connect"))
    )
    (net (code "77") (name "unconnected-(USB1-GND-Pad15)") (class "Default")
      (node (ref "USB1") (pin "15") (pinfunction "GND_15") (pintype "input+no_connect"))
    )
    (net (code "78") (name "unconnected-(USB1-GND-Pad16)") (class "Default")
      (node (ref "USB1") (pin "16") (pinfunction "GND_16") (pintype "input+no_connect"))
    )
    (net (code "79") (name "unconnected-(USB1-SBU1-PadA8)") (class "Default")
      (node (ref "USB1") (pin "A8") (pinfunction "SBU1_A8") (pintype "input+no_connect"))
    )
    (net (code "80") (name "unconnected-(USB1-SBU2-PadB8)") (class "Default")
      (node (ref "USB1") (pin "B8") (pinfunction "SBU2_B8") (pintype "input+no_connect"))
    )
  )
)
